# 01_Power_GPIO_Connector.net
KiCad netlist of a schematic drawn in Altium Designer
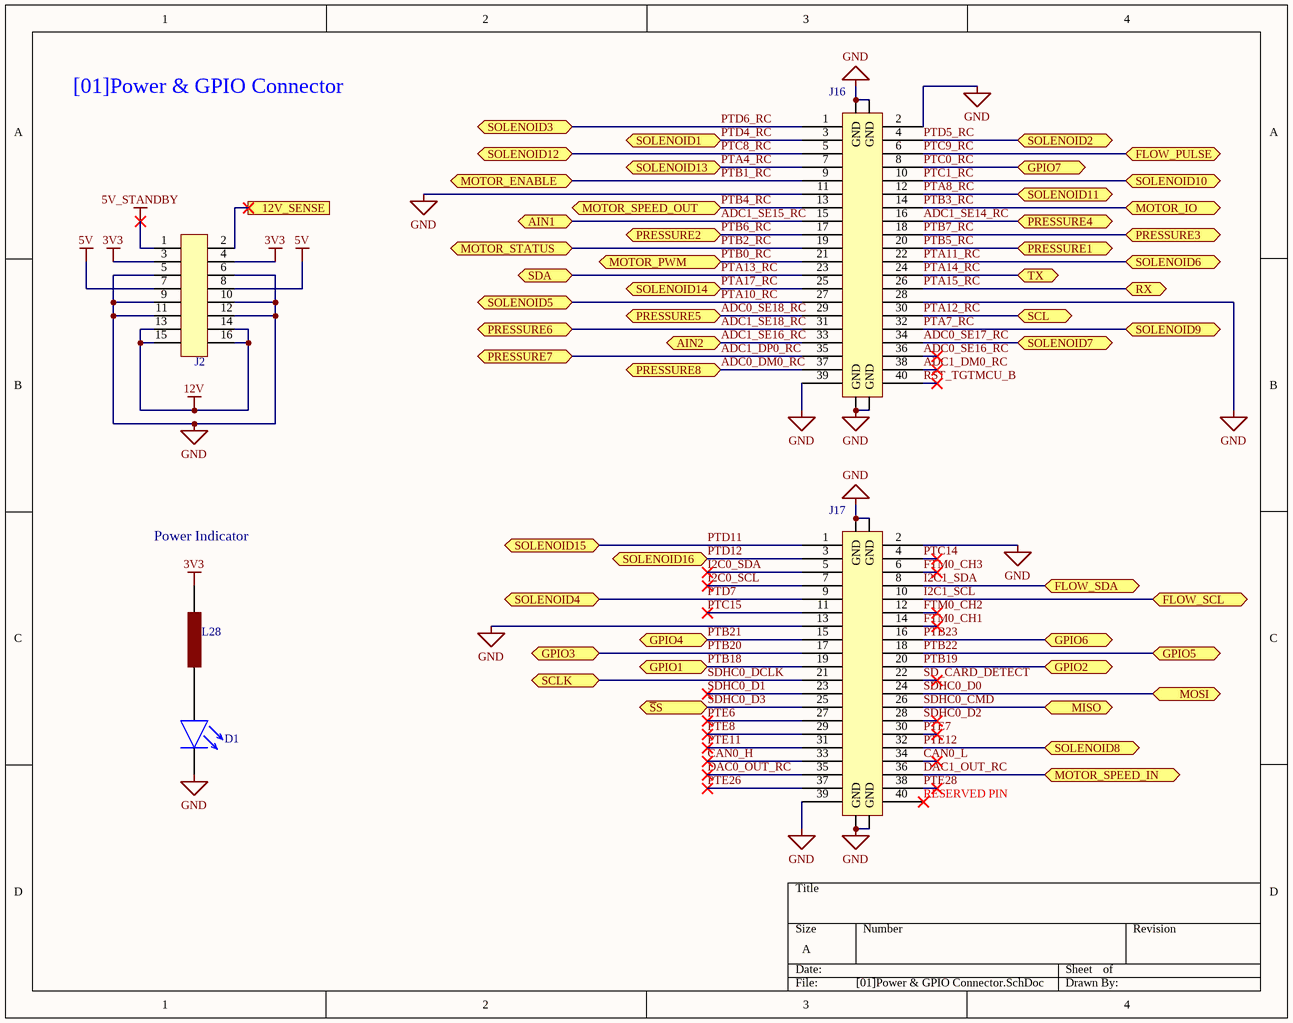
[diagram p0: [01]Power & GPIO Connector.SchDoc]

(export (version "E")
  (design (tool "Eeschema 10.0.6"))
  (components
    (comp (ref "D1")
      (value "XZFBB45S-9")
      (footprint "PLCC-2")
      (description "LED BLUE CLEAR 2PLCC SMD")
      (fields (field (name "MANUFACTURER") "SunLED"))
      (libsource (lib "AMMDK Parts") (part "XZFBB45S-9"))
    )
    (comp (ref "J2")
      (value "DF11-16DP-2DSA(01)")
      (footprint "DF11-16DP-2DSA(01)_FLIP")
      (description "Headers & Wire Housings 2MM V PCB HEADER 16P DR THRU-HOLE GLD")
      (fields (field (name "MANUFACTURER") "Hirose Connector"))
      (libsource (lib "AMMDK Parts") (part "DF11-16DP-2DSA(01)"))
    )
    (comp (ref "J16")
      (value "M55-7004042R")
      (footprint "M55-7004042R_FLIP")
      (description "Board to Board & Mezzanine Connectors 40P 1.27 SMC Male")
      (fields (field (name "MANUFACTURER") "Harwin"))
      (libsource (lib "AMMDK Parts") (part "M55-7004042R"))
    )
    (comp (ref "J17")
      (value "M55-7004042R")
      (footprint "M55-7004042R_FLIP")
      (description "Board to Board & Mezzanine Connectors 40P 1.27 SMC Male")
      (fields (field (name "MANUFACTURER") "Harwin"))
      (libsource (lib "AMMDK Parts") (part "M55-7004042R"))
    )
    (comp (ref "L28")
      (value "MH2029-300Y")
      (footprint "INDC2012X11N")
      (description "EMI Filter Beads, Chips & Arrays Impedance 30ohms IDC 3.0")
      (fields (field (name "MANUFACTURER") "Bourns") (field (name "TOLERANCE") "25 %"))
      (libsource (lib "AMMDK Parts") (part "MH2029-300Y"))
    )
  )
  (nets
    (net (code "1") (name "/12V_SENSE") (class "Default")
      (node (ref "J2") (pin "2") (pintype "power_in+no_connect"))
    )
    (net (code "2") (name "/ADC0_DM0_RC") (class "Default") (node (ref "J16") (pin "37") (pintype "passive")))
    (net (code "3") (name "/ADC0_SE16_RC") (class "Default")
      (node (ref "J16") (pin "36") (pintype "passive+no_connect"))
    )
    (net (code "4") (name "/ADC0_SE17_RC") (class "Default")
      (node (ref "J16") (pin "34") (pintype "passive"))
    )
    (net (code "5") (name "/ADC0_SE18_RC") (class "Default")
      (node (ref "J16") (pin "29") (pintype "passive"))
    )
    (net (code "6") (name "/ADC1_DM0_RC") (class "Default")
      (node (ref "J16") (pin "38") (pintype "passive+no_connect"))
    )
    (net (code "7") (name "/ADC1_DP0_RC") (class "Default") (node (ref "J16") (pin "35") (pintype "passive")))
    (net (code "8") (name "/ADC1_SE14_RC") (class "Default")
      (node (ref "J16") (pin "16") (pintype "passive"))
    )
    (net (code "9") (name "/ADC1_SE15_RC") (class "Default")
      (node (ref "J16") (pin "15") (pintype "passive"))
    )
    (net (code "10") (name "/ADC1_SE16_RC") (class "Default")
      (node (ref "J16") (pin "33") (pintype "passive"))
    )
    (net (code "11") (name "/ADC1_SE18_RC") (class "Default")
      (node (ref "J16") (pin "31") (pintype "passive"))
    )
    (net (code "12") (name "/CAN0_H") (class "Default")
      (node (ref "J17") (pin "33") (pintype "passive+no_connect"))
    )
    (net (code "13") (name "/CAN0_L") (class "Default")
      (node (ref "J17") (pin "34") (pintype "passive+no_connect"))
    )
    (net (code "14") (name "/DAC0_OUT_RC") (class "Default")
      (node (ref "J17") (pin "35") (pintype "passive+no_connect"))
    )
    (net (code "15") (name "/DAC1_OUT_RC") (class "Default")
      (node (ref "J17") (pin "36") (pintype "passive"))
    )
    (net (code "16") (name "/FTM0_CH1") (class "Default")
      (node (ref "J17") (pin "14") (pintype "passive+no_connect"))
    )
    (net (code "17") (name "/FTM0_CH2") (class "Default")
      (node (ref "J17") (pin "12") (pintype "passive+no_connect"))
    )
    (net (code "18") (name "/FTM0_CH3") (class "Default")
      (node (ref "J17") (pin "6") (pintype "passive+no_connect"))
    )
    (net (code "19") (name "/I2C0_SCL") (class "Default")
      (node (ref "J17") (pin "7") (pintype "passive+no_connect"))
    )
    (net (code "20") (name "/I2C0_SDA") (class "Default")
      (node (ref "J17") (pin "5") (pintype "passive+no_connect"))
    )
    (net (code "21") (name "/I2C1_SCL") (class "Default") (node (ref "J17") (pin "10") (pintype "passive")))
    (net (code "22") (name "/I2C1_SDA") (class "Default") (node (ref "J17") (pin "8") (pintype "passive")))
    (net (code "23") (name "/PTA4_RC") (class "Default") (node (ref "J16") (pin "7") (pintype "passive")))
    (net (code "24") (name "/PTA7_RC") (class "Default") (node (ref "J16") (pin "32") (pintype "passive")))
    (net (code "25") (name "/PTA8_RC") (class "Default") (node (ref "J16") (pin "12") (pintype "passive")))
    (net (code "26") (name "/PTA10_RC") (class "Default") (node (ref "J16") (pin "27") (pintype "passive")))
    (net (code "27") (name "/PTA11_RC") (class "Default") (node (ref "J16") (pin "22") (pintype "passive")))
    (net (code "28") (name "/PTA12_RC") (class "Default") (node (ref "J16") (pin "30") (pintype "passive")))
    (net (code "29") (name "/PTA13_RC") (class "Default") (node (ref "J16") (pin "23") (pintype "passive")))
    (net (code "30") (name "/PTA14_RC") (class "Default") (node (ref "J16") (pin "24") (pintype "passive")))
    (net (code "31") (name "/PTA15_RC") (class "Default") (node (ref "J16") (pin "26") (pintype "passive")))
    (net (code "32") (name "/PTA17_RC") (class "Default") (node (ref "J16") (pin "25") (pintype "passive")))
    (net (code "33") (name "/PTB0_RC") (class "Default") (node (ref "J16") (pin "21") (pintype "passive")))
    (net (code "34") (name "/PTB1_RC") (class "Default") (node (ref "J16") (pin "9") (pintype "passive")))
    (net (code "35") (name "/PTB2_RC") (class "Default") (node (ref "J16") (pin "19") (pintype "passive")))
    (net (code "36") (name "/PTB3_RC") (class "Default") (node (ref "J16") (pin "14") (pintype "passive")))
    (net (code "37") (name "/PTB4_RC") (class "Default") (node (ref "J16") (pin "13") (pintype "passive")))
    (net (code "38") (name "/PTB5_RC") (class "Default") (node (ref "J16") (pin "20") (pintype "passive")))
    (net (code "39") (name "/PTB6_RC") (class "Default") (node (ref "J16") (pin "17") (pintype "passive")))
    (net (code "40") (name "/PTB7_RC") (class "Default") (node (ref "J16") (pin "18") (pintype "passive")))
    (net (code "41") (name "/PTB18") (class "Default") (node (ref "J17") (pin "19") (pintype "passive")))
    (net (code "42") (name "/PTB19") (class "Default") (node (ref "J17") (pin "20") (pintype "passive")))
    (net (code "43") (name "/PTB20") (class "Default") (node (ref "J17") (pin "17") (pintype "passive")))
    (net (code "44") (name "/PTB21") (class "Default") (node (ref "J17") (pin "15") (pintype "passive")))
    (net (code "45") (name "/PTB22") (class "Default") (node (ref "J17") (pin "18") (pintype "passive")))
    (net (code "46") (name "/PTB23") (class "Default") (node (ref "J17") (pin "16") (pintype "passive")))
    (net (code "47") (name "/PTC0_RC") (class "Default") (node (ref "J16") (pin "8") (pintype "passive")))
    (net (code "48") (name "/PTC1_RC") (class "Default") (node (ref "J16") (pin "10") (pintype "passive")))
    (net (code "49") (name "/PTC8_RC") (class "Default") (node (ref "J16") (pin "5") (pintype "passive")))
    (net (code "50") (name "/PTC9_RC") (class "Default") (node (ref "J16") (pin "6") (pintype "passive")))
    (net (code "51") (name "/PTC14") (class "Default")
      (node (ref "J17") (pin "4") (pintype "passive+no_connect"))
    )
    (net (code "52") (name "/PTC15") (class "Default")
      (node (ref "J17") (pin "11") (pintype "passive+no_connect"))
    )
    (net (code "53") (name "/PTD4_RC") (class "Default") (node (ref "J16") (pin "3") (pintype "passive")))
    (net (code "54") (name "/PTD5_RC") (class "Default") (node (ref "J16") (pin "4") (pintype "passive")))
    (net (code "55") (name "/PTD6_RC") (class "Default") (node (ref "J16") (pin "1") (pintype "passive")))
    (net (code "56") (name "/PTD7") (class "Default") (node (ref "J17") (pin "9") (pintype "passive")))
    (net (code "57") (name "/PTD11") (class "Default") (node (ref "J17") (pin "1") (pintype "passive")))
    (net (code "58") (name "/PTD12") (class "Default") (node (ref "J17") (pin "3") (pintype "passive")))
    (net (code "59") (name "/PTE6") (class "Default")
      (node (ref "J17") (pin "27") (pintype "passive+no_connect"))
    )
    (net (code "60") (name "/PTE7") (class "Default")
      (node (ref "J17") (pin "30") (pintype "passive+no_connect"))
    )
    (net (code "61") (name "/PTE8") (class "Default")
      (node (ref "J17") (pin "29") (pintype "passive+no_connect"))
    )
    (net (code "62") (name "/PTE11") (class "Default")
      (node (ref "J17") (pin "31") (pintype "passive+no_connect"))
    )
    (net (code "63") (name "/PTE12") (class "Default") (node (ref "J17") (pin "32") (pintype "passive")))
    (net (code "64") (name "/PTE26") (class "Default")
      (node (ref "J17") (pin "37") (pintype "passive+no_connect"))
    )
    (net (code "65") (name "/PTE28") (class "Default")
      (node (ref "J17") (pin "38") (pintype "passive+no_connect"))
    )
    (net (code "66") (name "/RST_TGTMCU_B") (class "Default")
      (node (ref "J16") (pin "40") (pintype "passive+no_connect"))
    )
    (net (code "67") (name "/SDHC0_CMD") (class "Default") (node (ref "J17") (pin "26") (pintype "passive")))
    (net (code "68") (name "/SDHC0_D0") (class "Default") (node (ref "J17") (pin "24") (pintype "passive")))
    (net (code "69") (name "/SDHC0_D1") (class "Default")
      (node (ref "J17") (pin "23") (pintype "passive+no_connect"))
    )
    (net (code "70") (name "/SDHC0_D2") (class "Default")
      (node (ref "J17") (pin "28") (pintype "passive+no_connect"))
    )
    (net (code "71") (name "/SDHC0_D3") (class "Default") (node (ref "J17") (pin "25") (pintype "passive")))
    (net (code "72") (name "/SDHC0_DCLK") (class "Default") (node (ref "J17") (pin "21") (pintype "passive")))
    (net (code "73") (name "/SD_CARD_DETECT") (class "Default")
      (node (ref "J17") (pin "22") (pintype "passive+no_connect"))
    )
    (net (code "74") (name "3V3") (class "Default")
      (node (ref "J2") (pin "3") (pintype "power_in"))
      (node (ref "J2") (pin "4") (pintype "power_in"))
      (node (ref "L28") (pin "2") (pinfunction "2_2") (pintype "passive"))
    )
    (net (code "75") (name "5V") (class "Default")
      (node (ref "J2") (pin "7") (pintype "power_in"))
      (node (ref "J2") (pin "8") (pintype "power_in"))
    )
    (net (code "76") (name "5V_STANDBY") (class "Default") (node (ref "J2") (pin "1") (pintype "power_in")))
    (net (code "77") (name "12V") (class "Default")
      (node (ref "J2") (pin "13") (pintype "power_in"))
      (node (ref "J2") (pin "14") (pintype "power_in"))
      (node (ref "J2") (pin "15") (pintype "power_in"))
      (node (ref "J2") (pin "16") (pintype "power_in"))
    )
    (net (code "78") (name "GND") (class "Default")
      (node (ref "D1") (pin "2") (pinfunction "2_2") (pintype "passive"))
      (node (ref "J16") (pin "11") (pintype "passive"))
      (node (ref "J16") (pin "2") (pintype "passive"))
      (node (ref "J16") (pin "28") (pintype "passive"))
      (node (ref "J16") (pin "39") (pintype "passive"))
      (node (ref "J16") (pin "GND") (pinfunction "GND_GND") (pintype "passive"))
      (node (ref "J17") (pin "13") (pintype "passive"))
      (node (ref "J17") (pin "2") (pintype "passive"))
      (node (ref "J17") (pin "39") (pintype "passive"))
      (node (ref "J17") (pin "GND") (pinfunction "GND_GND") (pintype "passive"))
      (node (ref "J2") (pin "10") (pintype "power_in"))
      (node (ref "J2") (pin "11") (pintype "power_in"))
      (node (ref "J2") (pin "12") (pintype "power_in"))
      (node (ref "J2") (pin "5") (pintype "power_in"))
      (node (ref "J2") (pin "6") (pintype "power_in"))
      (node (ref "J2") (pin "9") (pintype "power_in"))
    )
    (net (code "79") (name "Net-(D1-Pad1)") (class "Default")
      (node (ref "D1") (pin "1") (pinfunction "1_1") (pintype "passive"))
      (node (ref "L28") (pin "1") (pinfunction "1_1") (pintype "passive"))
    )
    (net (code "80") (name "unconnected-(J17-Pad40)") (class "Default")
      (node (ref "J17") (pin "40") (pintype "passive+no_connect"))
    )
  )
)
